# Power_supply.net
KiCad netlist of a schematic drawn in Altium Designer
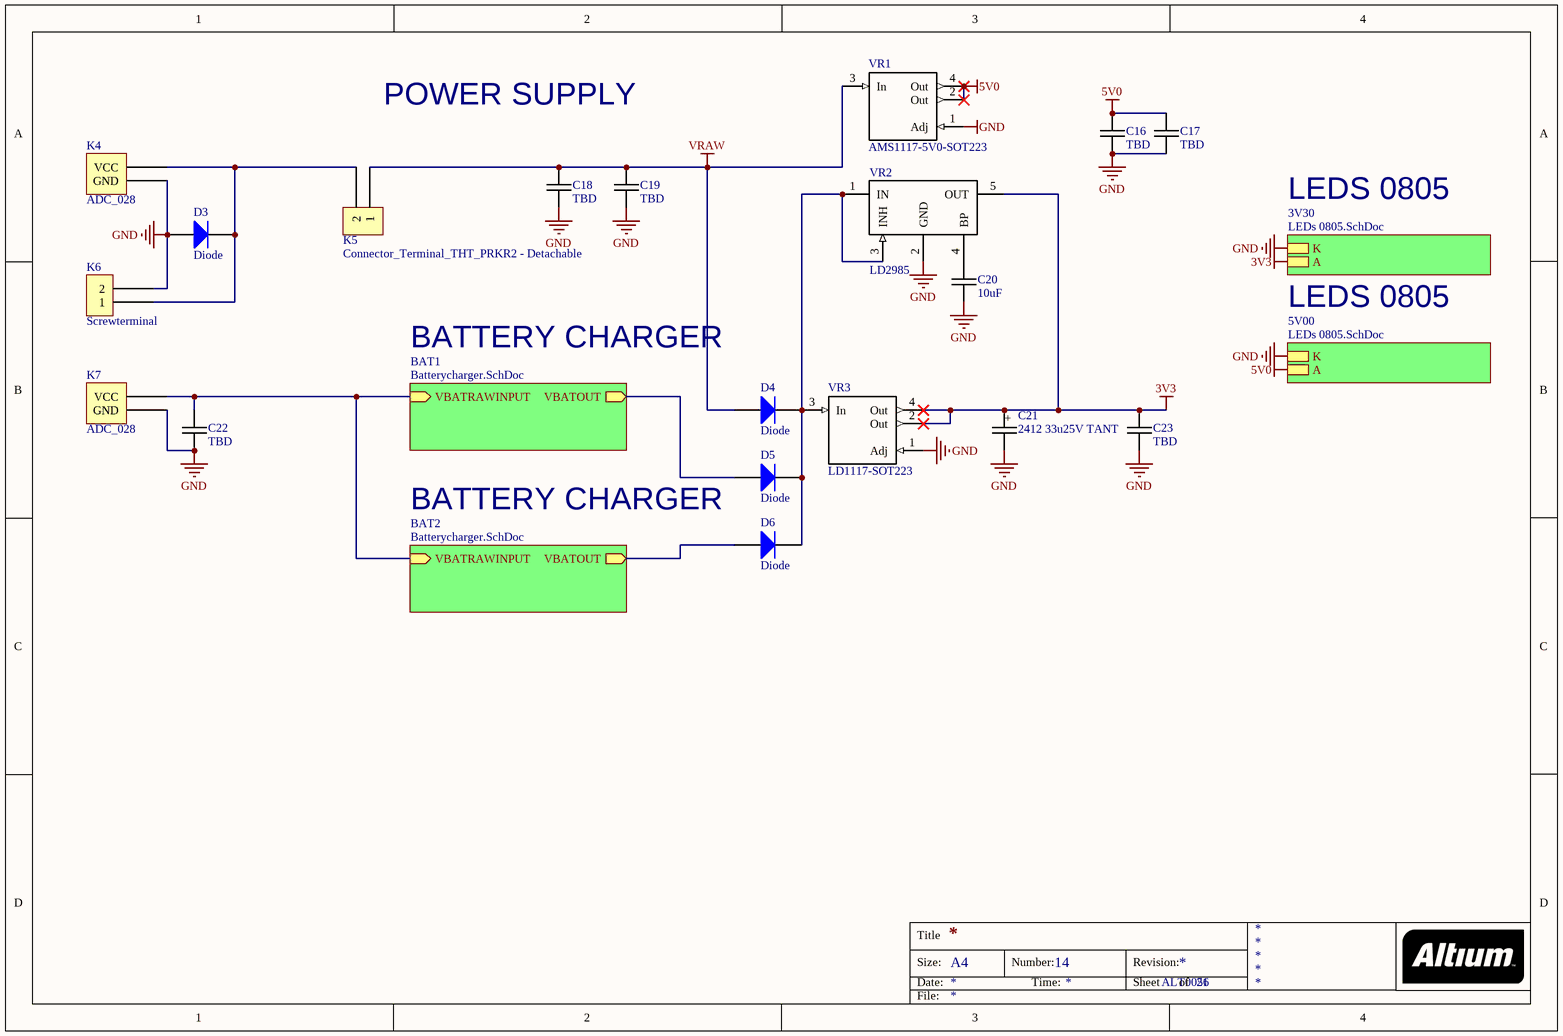
[diagram p0: Power supply.SchDoc]

(export (version "E")
  (design (tool "Eeschema 10.0.6"))
  (components
    (comp (ref "C16")
      (value "TBD")
      (footprint "1210C-GENERIC")
      (description "CAPACITOR 1210 CERAMIC VALUE TO BE DETERMINED")
      (libsource (lib "RVA_Altium_Library") (part "Passives_Capacitors_1210_1210C-TBD"))
    )
    (comp (ref "C17")
      (value "TBD")
      (footprint "1210C-GENERIC")
      (description "CAPACITOR 1210 CERAMIC VALUE TO BE DETERMINED")
      (libsource (lib "RVA_Altium_Library") (part "Passives_Capacitors_1210_1210C-TBD"))
    )
    (comp (ref "C18")
      (value "TBD")
      (footprint "1210C-GENERIC")
      (description "CAPACITOR 1210 CERAMIC VALUE TO BE DETERMINED")
      (libsource (lib "RVA_Altium_Library") (part "Passives_Capacitors_1210_1210C-TBD"))
    )
    (comp (ref "C19")
      (value "TBD")
      (footprint "1210C-GENERIC")
      (description "CAPACITOR 1210 CERAMIC VALUE TO BE DETERMINED")
      (libsource (lib "RVA_Altium_Library") (part "Passives_Capacitors_1210_1210C-TBD"))
    )
    (comp (ref "C20")
      (value "10uF")
      (footprint "0603C-GENERIC")
      (description "CAPACITOR 0603 CERAMIC")
      (fields
        (field (name "MANUFACTURER PART NUMBER") "C1608X5R0J106M")
        (field (name "MANUFACTURER") "TDK Corporation")
      )
      (libsource (lib "RVA_Altium_Library") (part "0603C-10UF-10V-X5R-TDK"))
    )
    (comp (ref "C21")
      (value "2412 33u25V TANT")
      (footprint "2412C+_TANTAL-33u25V")
      (libsource (lib "RVA_Altium_Library") (part "2412C-TANTAL SIZE C-33u25V"))
    )
    (comp (ref "C22")
      (value "TBD")
      (footprint "1210C-GENERIC")
      (description "CAPACITOR 1210 CERAMIC VALUE TO BE DETERMINED")
      (libsource (lib "RVA_Altium_Library") (part "Passives_Capacitors_1210_1210C-TBD"))
    )
    (comp (ref "C23")
      (value "TBD")
      (footprint "1210C-GENERIC")
      (description "CAPACITOR 1210 CERAMIC VALUE TO BE DETERMINED")
      (libsource (lib "RVA_Altium_Library") (part "Passives_Capacitors_1210_1210C-TBD"))
    )
    (comp (ref "D3")
      (value "Diode")
      (footprint "SMB")
      (description "Default Diode")
      (fields (field (name "PUBLISHER") "Altium Limited"))
      (libsource (lib "Miscellaneous Devices") (part "Diode"))
    )
    (comp (ref "D4")
      (value "Diode")
      (footprint "SMB")
      (description "Default Diode")
      (fields (field (name "PUBLISHER") "Altium Limited"))
      (libsource (lib "Miscellaneous Devices") (part "Diode"))
    )
    (comp (ref "D5")
      (value "Diode")
      (footprint "SMB")
      (description "Default Diode")
      (fields (field (name "PUBLISHER") "Altium Limited"))
      (libsource (lib "Miscellaneous Devices") (part "Diode"))
    )
    (comp (ref "D6")
      (value "Diode")
      (footprint "SMB")
      (description "Default Diode")
      (fields (field (name "PUBLISHER") "Altium Limited"))
      (libsource (lib "Miscellaneous Devices") (part "Diode"))
    )
    (comp (ref "K4")
      (value "ADC_028")
      (footprint "ADC-028")
      (description "5.5mm SMD")
      (libsource (lib "RVA_Altium_Library") (part "ADC_028"))
    )
    (comp (ref "K5")
      (value "Connector_Terminal_THT_PRKR2 - Detachable")
      (footprint "PRKR2-DET")
      (libsource (lib "RVA_Altium_Library") (part "Connector_Terminal_THT_PRKR2 - Detachable"))
    )
    (comp (ref "K6")
      (value "Screwterminal")
      (footprint "PRKR2-DET")
      (libsource (lib "") (part "Connector_Terminal_THT_PRKR2 - Detachable_1"))
    )
    (comp (ref "K7")
      (value "ADC_028")
      (footprint "ADC-028")
      (description "5.5mm SMD")
      (libsource (lib "RVA_Altium_Library") (part "ADC_028"))
    )
    (comp (ref "VR1")
      (value "AMS1117-5V0-SOT223")
      (footprint "SOT223")
      (libsource (lib "RVA_Altium_Library") (part "LD1117-SOT223"))
    )
    (comp (ref "VR2")
      (value "LD2985")
      (footprint "SOT23-5")
      (description "Low Noise Low Drop Voltage Regulator  with Inhibit")
      (libsource (lib "RVA_Altium_Library") (part "LD2985"))
    )
    (comp (ref "VR3")
      (value "LD1117-SOT223")
      (footprint "SOT223")
      (libsource (lib "vh_altium_library") (part "LD1117-SOT223"))
    )
  )
  (nets
    (net (code "1") (name "/VBATOUT") (class "Default")
      (node (ref "D5") (pin "1") (pinfunction "A_1") (pintype "passive"))
    )
    (net (code "2") (name "/VBATOUT_1") (class "Default")
      (node (ref "D6") (pin "1") (pinfunction "A_1") (pintype "passive"))
    )
    (net (code "3") (name "/VBATRAWINPUT") (class "Default")
      (node (ref "C22") (pin "1") (pintype "passive"))
      (node (ref "K7") (pin "VCC") (pinfunction "VCC_VCC") (pintype "power_in"))
    )
    (net (code "4") (name "3V3") (class "Default")
      (node (ref "C21") (pin "1") (pintype "passive"))
      (node (ref "C23") (pin "1") (pintype "passive"))
      (node (ref "VR2") (pin "5") (pinfunction "OUT_5") (pintype "power_in"))
      (node (ref "VR3") (pin "2") (pinfunction "Out_2") (pintype "output"))
      (node (ref "VR3") (pin "4") (pinfunction "Out_4") (pintype "output"))
    )
    (net (code "5") (name "5V0") (class "Default")
      (node (ref "C16") (pin "1") (pintype "passive"))
      (node (ref "C17") (pin "1") (pintype "passive"))
      (node (ref "VR1") (pin "2") (pinfunction "Out_2") (pintype "output"))
      (node (ref "VR1") (pin "4") (pinfunction "Out_4") (pintype "output"))
    )
    (net (code "6") (name "GND") (class "Default")
      (node (ref "C16") (pin "2") (pintype "passive"))
      (node (ref "C17") (pin "2") (pintype "passive"))
      (node (ref "C18") (pin "2") (pintype "passive"))
      (node (ref "C19") (pin "2") (pintype "passive"))
      (node (ref "C20") (pin "2") (pintype "passive"))
      (node (ref "C21") (pin "2") (pintype "passive"))
      (node (ref "C22") (pin "2") (pintype "passive"))
      (node (ref "C23") (pin "2") (pintype "passive"))
      (node (ref "D3") (pin "1") (pinfunction "A_1") (pintype "passive"))
      (node (ref "K4") (pin "GND") (pinfunction "GND_GND") (pintype "power_in"))
      (node (ref "K6") (pin "2") (pinfunction "2_2") (pintype "passive"))
      (node (ref "K7") (pin "GND") (pinfunction "GND_GND") (pintype "power_in"))
      (node (ref "VR1") (pin "1") (pinfunction "Adj_1") (pintype "input"))
      (node (ref "VR2") (pin "2") (pinfunction "GND_2") (pintype "power_in"))
      (node (ref "VR3") (pin "1") (pinfunction "Adj_1") (pintype "input"))
    )
    (net (code "7") (name "Net-(D3-K)") (class "Default")
      (node (ref "D3") (pin "2") (pinfunction "K_2") (pintype "passive"))
      (node (ref "K4") (pin "VCC") (pinfunction "VCC_VCC") (pintype "power_in"))
      (node (ref "K5") (pin "2") (pinfunction "2_2") (pintype "passive"))
      (node (ref "K6") (pin "1") (pinfunction "1_1") (pintype "passive"))
    )
    (net (code "8") (name "Net-(D4-K)") (class "Default")
      (node (ref "D4") (pin "2") (pinfunction "K_2") (pintype "passive"))
      (node (ref "D5") (pin "2") (pinfunction "K_2") (pintype "passive"))
      (node (ref "D6") (pin "2") (pinfunction "K_2") (pintype "passive"))
      (node (ref "VR2") (pin "1") (pinfunction "IN_1") (pintype "power_in"))
      (node (ref "VR2") (pin "3") (pinfunction "INH_3") (pintype "input"))
      (node (ref "VR3") (pin "3") (pinfunction "In_3") (pintype "input"))
    )
    (net (code "9") (name "Net-(VR2-BP)") (class "Default")
      (node (ref "C20") (pin "1") (pintype "passive"))
      (node (ref "VR2") (pin "4") (pinfunction "BP_4") (pintype "power_in"))
    )
    (net (code "10") (name "VRAW") (class "Default")
      (node (ref "C18") (pin "1") (pintype "passive"))
      (node (ref "C19") (pin "1") (pintype "passive"))
      (node (ref "D4") (pin "1") (pinfunction "A_1") (pintype "passive"))
      (node (ref "K5") (pin "1") (pinfunction "1_1") (pintype "passive"))
      (node (ref "VR1") (pin "3") (pinfunction "In_3") (pintype "input"))
    )
  )
)
